# FTDI.net
KiCad netlist of a schematic drawn in Altium Designer
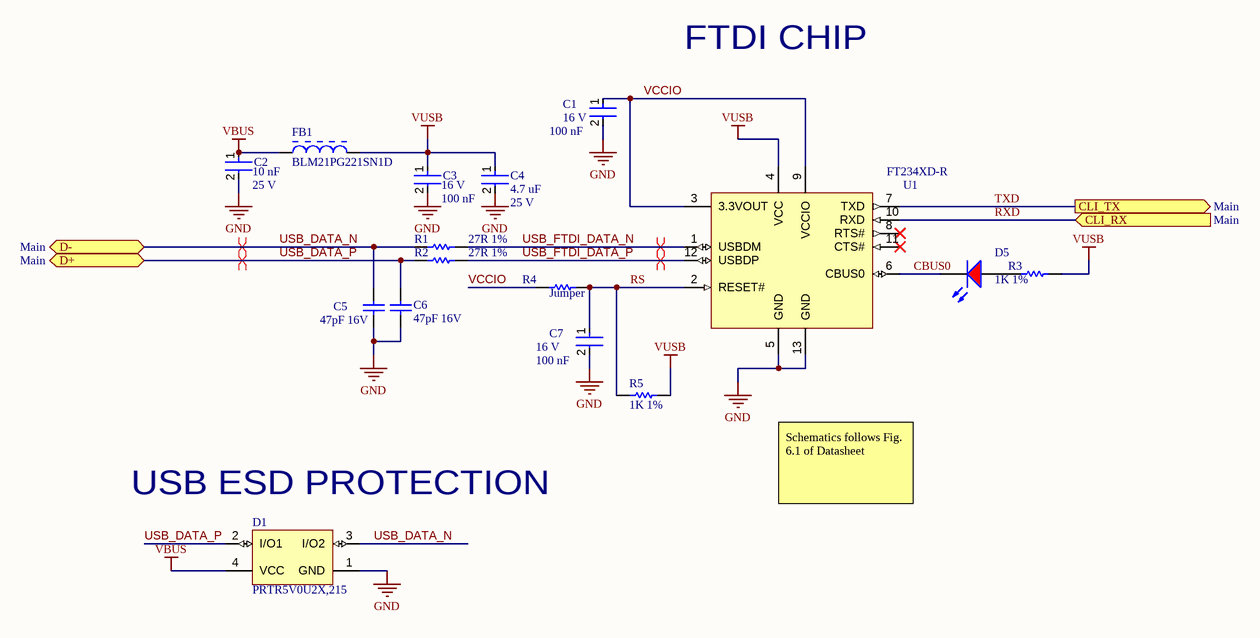
[diagram p0: FTDI.SchDoc]

(export (version "E")
  (design (tool "Eeschema 10.0.6"))
  (components
    (comp (ref "C1")
      (value "100 nF")
      (footprint "FP-CC0603-DA-MFG")
      (description "CAP CER 0.1UF 16V X7R 0603")
      (fields
        (field (name "TOLERANCE") "0.1")
        (field (name "VOLTAGE") "16 V")
        (field (name "MANUFACTURER") "YAGEO")
      )
      (libsource (lib "Altium Content Vault") (part "11868f565c42a9108669ba33697ecf6"))
    )
    (comp (ref "C2")
      (value "CC0603MRX7R8BB103")
      (footprint "FP-CC0603-DA-MFG")
      (description "CAP CER 10000PF 25V X7R 0603")
      (fields
        (field (name "CAPACITANCE") "10 nF")
        (field (name "TOLERANCE") "0.2")
        (field (name "VOLTAGE") "25 V")
        (field (name "OCTOPART") "https://octopart.com/cc0603mrx7r8bb103-yageo-18816920")
      )
      (libsource (lib "Altium Content Vault") (part "11868f565c42a9108669ba33697ecf6"))
    )
    (comp (ref "C3")
      (value "100 nF")
      (footprint "FP-CC0603-DA-MFG")
      (description "CAP CER 0.1UF 16V X7R 0603")
      (fields
        (field (name "TOLERANCE") "0.1")
        (field (name "VOLTAGE") "16 V")
        (field (name "MANUFACTURER") "YAGEO")
      )
      (libsource (lib "Altium Content Vault") (part "11868f565c42a9108669ba33697ecf6"))
    )
    (comp (ref "C4")
      (value "CC0805KKX7R8BB475")
      (footprint "FP-CC0805-0_85-MFG")
      (description "CAP CER 4.7UF 25V X7R 0805")
      (fields
        (field (name "OCTOPART") "https://octopart.com/cc0805kkx7r8bb475-yageo-51849247")
        (field (name "CAPACITANCE") "4.7 uF")
        (field (name "MANUFACTURER") "Yageo")
        (field (name "VOLTAGE RATING") "25 V")
      )
      (libsource (lib "Altium Content Vault") (part "11868f565c42a9108669ba33697ecf6"))
    )
    (comp (ref "C5")
      (value "47pF 16V")
      (footprint "CAPC0603(1608)100_N")
      (description "CAP 47pF 16V ±0.5pF 0603 (1608 Metric) Thickness 1mm SMD")
      (fields (field (name "TOLERANCE") "Â±0.5pF"))
      (libsource (lib "Altium Content Vault") (part "CAP"))
    )
    (comp (ref "C6")
      (value "47pF 16V")
      (footprint "CAPC0603(1608)100_N")
      (description "CAP 47pF 16V ±0.5pF 0603 (1608 Metric) Thickness 1mm SMD")
      (fields (field (name "TOLERANCE") "Â±0.5pF"))
      (libsource (lib "Altium Content Vault") (part "CAP"))
    )
    (comp (ref "C7")
      (value "100 nF")
      (footprint "FP-CC0603-DA-MFG")
      (description "CAP CER 0.1UF 16V X7R 0603")
      (fields
        (field (name "TOLERANCE") "0.1")
        (field (name "VOLTAGE") "16 V")
        (field (name "MANUFACTURER") "YAGEO")
      )
      (libsource (lib "Altium Content Vault") (part "11868f565c42a9108669ba33697ecf6"))
    )
    (comp (ref "D1")
      (value "PRTR5V0U2X,215")
      (footprint "NXP-SOT143B-4_V")
      (fields (field (name "MANUFACTURER") "NXP Semiconductors"))
      (libsource (lib "Altium Content Vault") (part "NXP-PRTR5V0U2X,215-4"))
    )
    (comp (ref "D5")
      (value "LTST-C170CKT")
      (footprint "LTST-C170CKT_V")
      (description "LED Uni-Color Red, 100 mW, 200 mA, -55 to 85 degC, 2-Pin SMD, RoHS, Tape and Reel")
      (fields (field (name "MANUFACTURER") "Lite-On"))
      (libsource (lib "Altium Content Vault") (part "LED-RED-AK-2"))
    )
    (comp (ref "FB1")
      (value "BLM21PG221SN1D")
      (footprint "MURA-BLM21-B20-CHIP-2_V2")
      (fields (field (name "MANUFACTURER") "Murata"))
      (libsource (lib "Altium Content Vault") (part "MURA-FB-2"))
    )
    (comp (ref "R1")
      (value "27R 1%")
      (footprint "RESC0603(1608)_N")
      (description "27R 0.1W 1% 0603 (1608 Metric)  SMD")
      (fields (field (name "TOLERANCE") "1 %") (field (name "POWER") "0.1 W"))
      (libsource (lib "Altium Content Vault") (part "RES"))
    )
    (comp (ref "R2")
      (value "27R 1%")
      (footprint "RESC0603(1608)_N")
      (description "27R 0.1W 1% 0603 (1608 Metric)  SMD")
      (fields (field (name "TOLERANCE") "1 %") (field (name "POWER") "0.1 W"))
      (libsource (lib "Altium Content Vault") (part "RES"))
    )
    (comp (ref "R3")
      (value "1K 1%")
      (footprint "RESC0603(1608)_N")
      (description "1K 0.1W 1% 0603 (1608 Metric)  SMD")
      (fields (field (name "TOLERANCE") "1 %") (field (name "POWER") "0.1 W"))
      (libsource (lib "Altium Content Vault") (part "RES"))
    )
    (comp (ref "R4")
      (value "Jumper")
      (footprint "RESC0603(1608)_N")
      (description "Jumper 0603 (1608 Metric)")
      (fields (field (name "POWER") "None"))
      (libsource (lib "Altium Content Vault") (part "RES"))
    )
    (comp (ref "R5")
      (value "1K 1%")
      (footprint "RESC0603(1608)_N")
      (description "1K 0.1W 1% 0603 (1608 Metric)  SMD")
      (fields (field (name "TOLERANCE") "1 %") (field (name "POWER") "0.1 W"))
      (libsource (lib "Altium Content Vault") (part "RES"))
    )
    (comp (ref "U1")
      (value "FT234XD-R")
      (footprint "DFN-12_V")
      (description "FT234XD USB to BASIC UART IC, -40 to +85 degC, 12-Pin DFN, Pb-Free, Tape and Reel")
      (fields (field (name "MANUFACTURER") "FTDI"))
      (libsource (lib "Altium Content Vault") (part "FTDI-FT234XD-DFN-12"))
    )
  )
  (nets
    (net (code "1") (name "/CBUS0") (class "Default")
      (node (ref "D5") (pin "2") (pinfunction "K_2") (pintype "passive"))
      (node (ref "U1") (pin "6") (pinfunction "CBUS0_6") (pintype "bidirectional"))
    )
    (net (code "2") (name "/RS") (class "Default")
      (node (ref "C7") (pin "1") (pinfunction "1_1") (pintype "passive"))
      (node (ref "R4") (pin "2") (pinfunction "2_2") (pintype "passive"))
      (node (ref "R5") (pin "2") (pinfunction "2_2") (pintype "passive"))
      (node (ref "U1") (pin "2") (pinfunction "RESET#_2") (pintype "input"))
    )
    (net (code "3") (name "/RXD") (class "Default")
      (node (ref "U1") (pin "10") (pinfunction "RXD_10") (pintype "input"))
    )
    (net (code "4") (name "/TXD") (class "Default")
      (node (ref "U1") (pin "7") (pinfunction "TXD_7") (pintype "output"))
    )
    (net (code "5") (name "/USB_DATA_N") (class "Default")
      (node (ref "C5") (pin "2") (pinfunction "2_2") (pintype "passive"))
      (node (ref "D1") (pin "3") (pinfunction "I/O2_3") (pintype "bidirectional"))
      (node (ref "R1") (pin "1") (pinfunction "1_1") (pintype "passive"))
    )
    (net (code "6") (name "/USB_DATA_P") (class "Default")
      (node (ref "C6") (pin "2") (pinfunction "2_2") (pintype "passive"))
      (node (ref "D1") (pin "2") (pinfunction "I/O1_2") (pintype "bidirectional"))
      (node (ref "R2") (pin "1") (pinfunction "1_1") (pintype "passive"))
    )
    (net (code "7") (name "/USB_FTDI_DATA_N") (class "Default")
      (node (ref "R1") (pin "2") (pinfunction "2_2") (pintype "passive"))
      (node (ref "U1") (pin "1") (pinfunction "USBDM_1") (pintype "bidirectional"))
    )
    (net (code "8") (name "/USB_FTDI_DATA_P") (class "Default")
      (node (ref "R2") (pin "2") (pinfunction "2_2") (pintype "passive"))
      (node (ref "U1") (pin "12") (pinfunction "USBDP_12") (pintype "bidirectional"))
    )
    (net (code "9") (name "/VCCIO") (class "Default")
      (node (ref "C1") (pin "1") (pinfunction "1_1") (pintype "passive"))
      (node (ref "R4") (pin "1") (pinfunction "1_1") (pintype "passive"))
      (node (ref "U1") (pin "3") (pinfunction "3.3VOUT_3") (pintype "power_in"))
      (node (ref "U1") (pin "9") (pinfunction "VCCIO_9") (pintype "power_in"))
    )
    (net (code "10") (name "GND") (class "Default")
      (node (ref "C1") (pin "2") (pinfunction "2_2") (pintype "passive"))
      (node (ref "C2") (pin "2") (pinfunction "2_2") (pintype "passive"))
      (node (ref "C3") (pin "2") (pinfunction "2_2") (pintype "passive"))
      (node (ref "C4") (pin "2") (pinfunction "2_2") (pintype "passive"))
      (node (ref "C5") (pin "1") (pinfunction "1_1") (pintype "passive"))
      (node (ref "C6") (pin "1") (pinfunction "1_1") (pintype "passive"))
      (node (ref "C7") (pin "2") (pinfunction "2_2") (pintype "passive"))
      (node (ref "D1") (pin "1") (pinfunction "GND_1") (pintype "power_in"))
      (node (ref "U1") (pin "13") (pinfunction "GND_13") (pintype "power_in"))
      (node (ref "U1") (pin "5") (pinfunction "GND_5") (pintype "power_in"))
    )
    (net (code "11") (name "Net-(D5-A)") (class "Default")
      (node (ref "D5") (pin "1") (pinfunction "A_1") (pintype "passive"))
      (node (ref "R3") (pin "1") (pinfunction "1_1") (pintype "passive"))
    )
    (net (code "12") (name "VBUS") (class "Default")
      (node (ref "C2") (pin "1") (pinfunction "1_1") (pintype "passive"))
      (node (ref "D1") (pin "4") (pinfunction "VCC_4") (pintype "power_in"))
      (node (ref "FB1") (pin "1") (pinfunction "1_1") (pintype "passive"))
    )
    (net (code "13") (name "VUSB") (class "Default")
      (node (ref "C3") (pin "1") (pinfunction "1_1") (pintype "passive"))
      (node (ref "C4") (pin "1") (pinfunction "1_1") (pintype "passive"))
      (node (ref "FB1") (pin "2") (pinfunction "2_2") (pintype "passive"))
      (node (ref "R3") (pin "2") (pinfunction "2_2") (pintype "passive"))
      (node (ref "R5") (pin "1") (pinfunction "1_1") (pintype "passive"))
      (node (ref "U1") (pin "4") (pinfunction "VCC_4") (pintype "power_in"))
    )
    (net (code "14") (name "unconnected-(U1-CTS#-Pad11)") (class "Default")
      (node (ref "U1") (pin "11") (pinfunction "CTS#_11") (pintype "input+no_connect"))
    )
    (net (code "15") (name "unconnected-(U1-RTS#-Pad8)") (class "Default")
      (node (ref "U1") (pin "8") (pinfunction "RTS#_8") (pintype "output+no_connect"))
    )
  )
)
